# auxblox.net
KiCad netlist of a schematic drawn in EAGLE
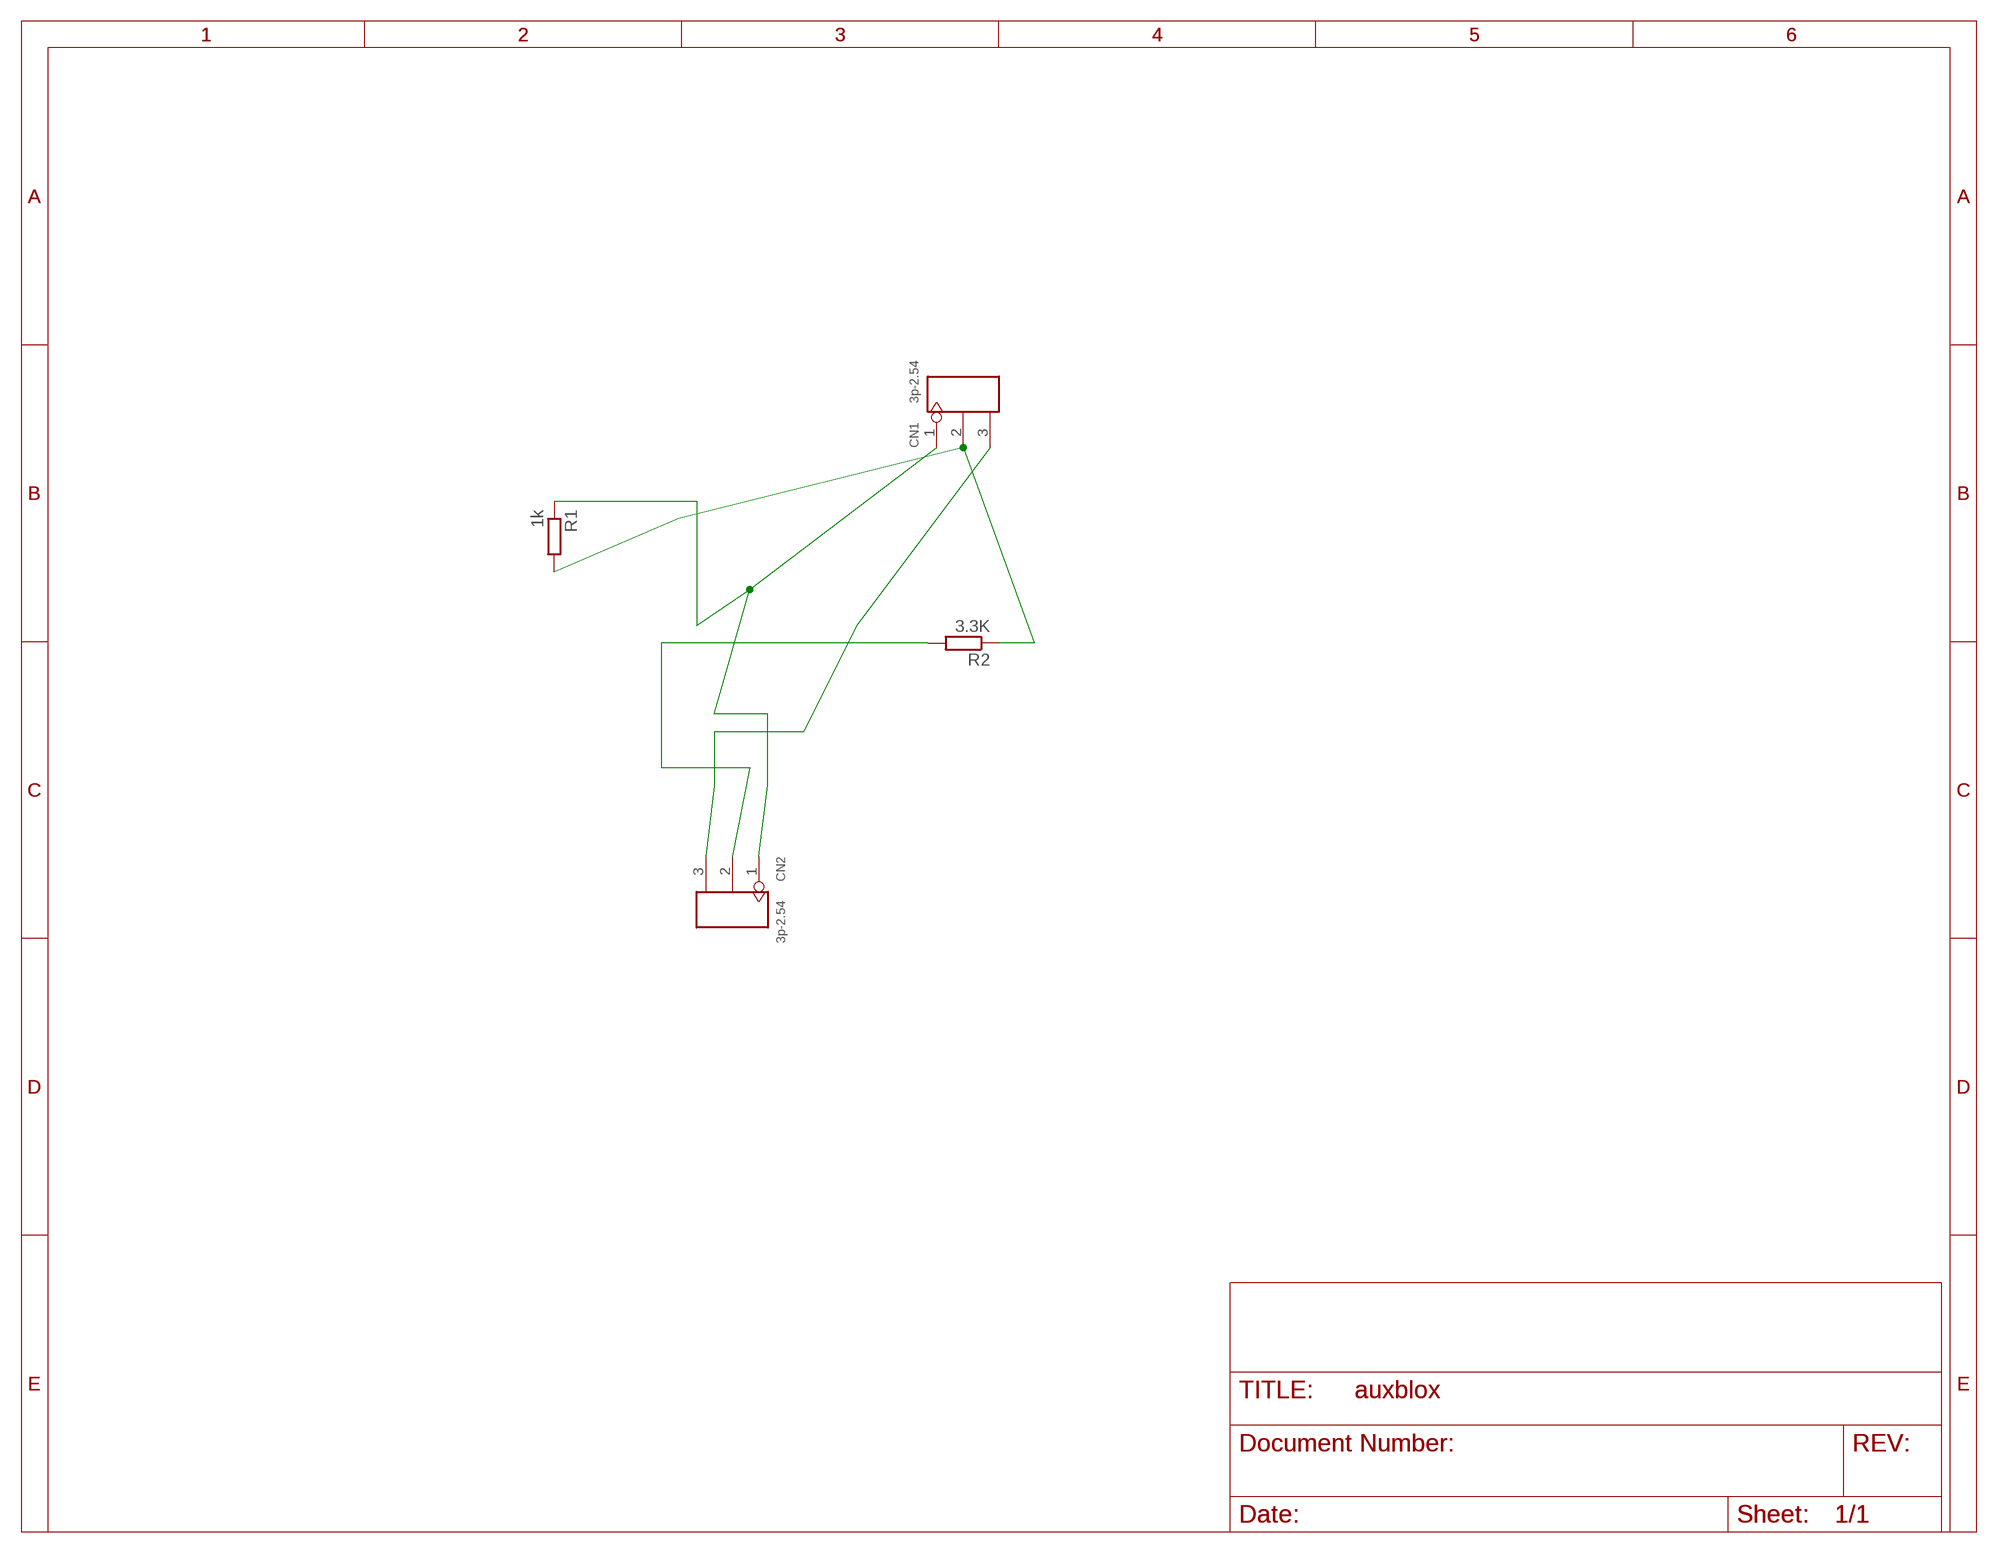
[diagram p0: schematic, sheet 1]

(export (version "E")
  (design (tool "Eeschema 10.0.6"))
  (components
    (comp (ref "CN1")
      (value "3p-2.54")
      (footprint "eagle-import:H3-2.54")
      (libsource (lib "eagle-import") (part "DIP-BLACK-MALE-HEADER-VERT(3P-2.54)"))
    )
    (comp (ref "CN2")
      (value "3p-2.54")
      (footprint "eagle-import:H3-2.54")
      (libsource (lib "eagle-import") (part "DIP-BLACK-MALE-HEADER-VERT(3P-2.54)"))
    )
    (comp (ref "R1")
      (value "1k")
      (footprint "eagle-import:R0805")
      (libsource (lib "eagle-import") (part "R-EU_R0805"))
    )
    (comp (ref "R2")
      (value "3.3K")
      (footprint "eagle-import:R0805")
      (libsource (lib "eagle-import") (part "R-EU_R0805"))
    )
  )
  (nets
    (net (code "1") (name "Net-(CN1-P$1)") (class "Default")
      (node (ref "CN1") (pin "1") (pinfunction "P$1_1") (pintype "bidirectional"))
      (node (ref "CN2") (pin "1") (pinfunction "P$1_1") (pintype "bidirectional"))
      (node (ref "R1") (pin "1") (pinfunction "1_1") (pintype "passive"))
    )
    (net (code "2") (name "Net-(CN1-P$2)") (class "Default")
      (node (ref "CN1") (pin "2") (pinfunction "P$2_2") (pintype "bidirectional"))
      (node (ref "R1") (pin "2") (pinfunction "2_2") (pintype "passive"))
      (node (ref "R2") (pin "1") (pinfunction "1_1") (pintype "passive"))
    )
    (net (code "3") (name "Net-(CN1-P$3)") (class "Default")
      (node (ref "CN1") (pin "3") (pinfunction "P$3_3") (pintype "bidirectional"))
      (node (ref "CN2") (pin "3") (pinfunction "P$3_3") (pintype "bidirectional"))
    )
    (net (code "4") (name "Net-(CN2-P$2)") (class "Default")
      (node (ref "CN2") (pin "2") (pinfunction "P$2_2") (pintype "bidirectional"))
      (node (ref "R2") (pin "2") (pinfunction "2_2") (pintype "passive"))
    )
  )
)
